# GECBalloonMCUFlightBoard_REV1_0_8-22-18.net
KiCad netlist of a schematic drawn in EAGLE
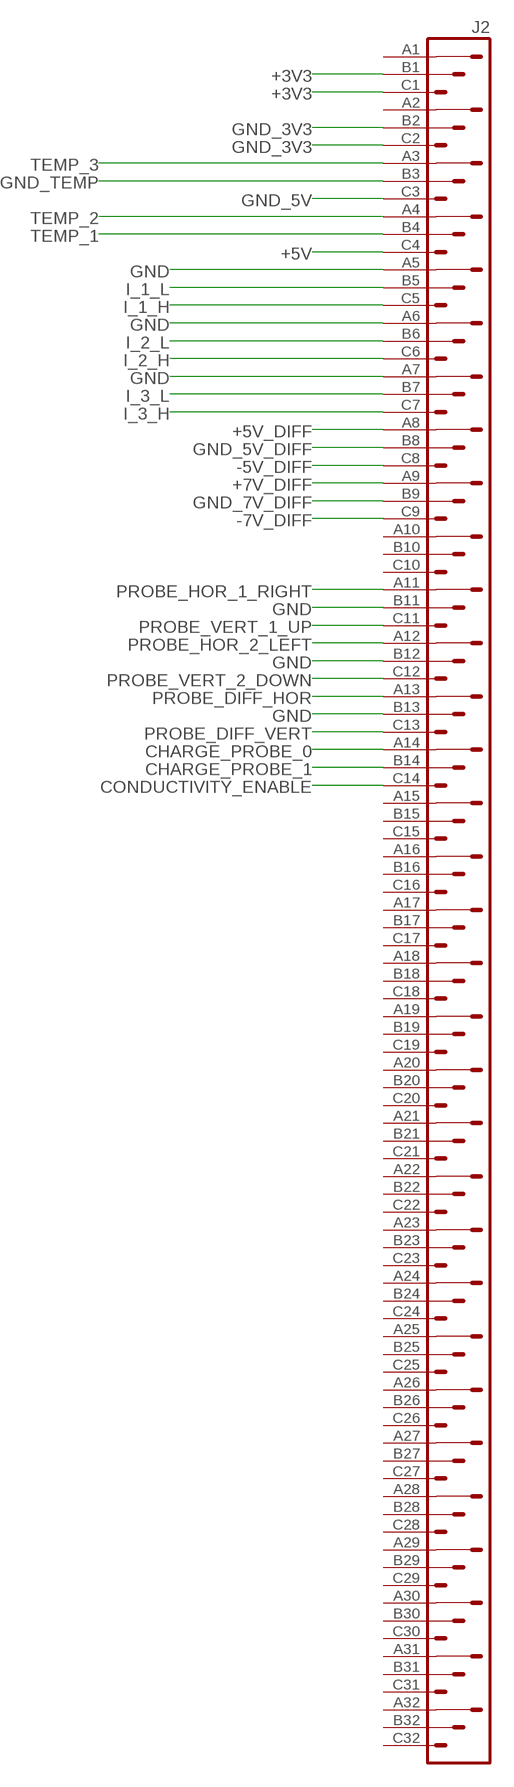
[diagram p0: schematic, sheet 1, part 1 of 2]
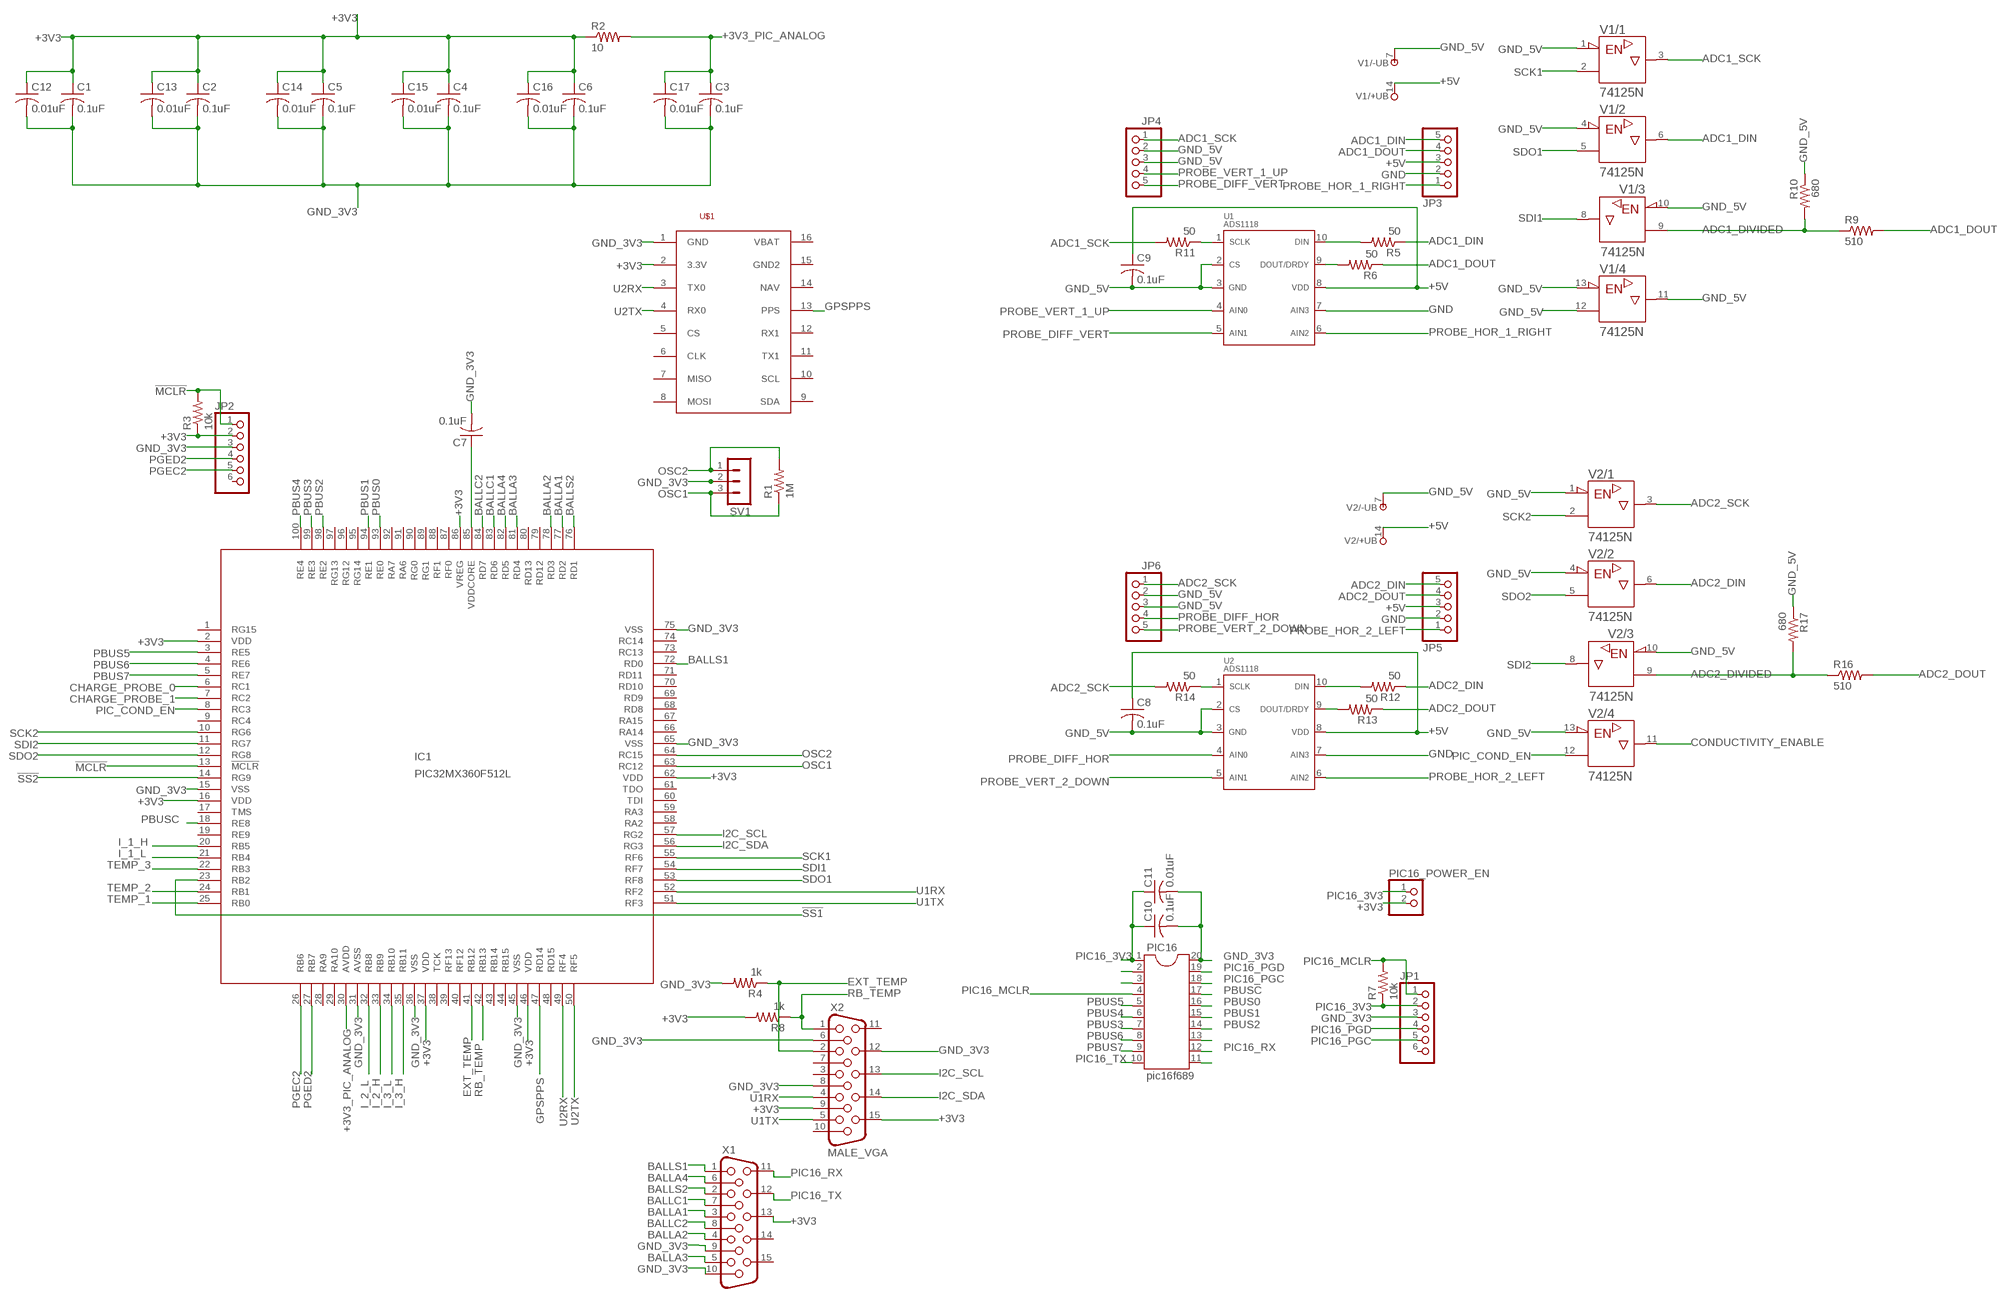
[diagram p1: schematic, sheet 1, part 2 of 2]

(export (version "E")
  (design (tool "Eeschema 10.0.6"))
  (components
    (comp (ref "C1")
      (value "0.1uF")
      (footprint "eagle-import:C1206")
      (libsource (lib "eagle-import") (part "C-USC1206"))
    )
    (comp (ref "C2")
      (value "0.1uF")
      (footprint "eagle-import:C1206")
      (libsource (lib "eagle-import") (part "C-USC1206"))
    )
    (comp (ref "C3")
      (value "0.1uF")
      (footprint "eagle-import:C1206")
      (libsource (lib "eagle-import") (part "C-USC1206"))
    )
    (comp (ref "C4")
      (value "0.1uF")
      (footprint "eagle-import:C1206")
      (libsource (lib "eagle-import") (part "C-USC1206"))
    )
    (comp (ref "C5")
      (value "0.1uF")
      (footprint "eagle-import:C1206")
      (libsource (lib "eagle-import") (part "C-USC1206"))
    )
    (comp (ref "C6")
      (value "0.1uF")
      (footprint "eagle-import:C1206")
      (libsource (lib "eagle-import") (part "C-USC1206"))
    )
    (comp (ref "C7")
      (value "0.1uF")
      (footprint "eagle-import:C1206")
      (libsource (lib "eagle-import") (part "C-USC1206"))
    )
    (comp (ref "C8")
      (value "0.1uF")
      (footprint "eagle-import:C1206")
      (libsource (lib "eagle-import") (part "C-USC1206"))
    )
    (comp (ref "C9")
      (value "0.1uF")
      (footprint "eagle-import:C1206")
      (libsource (lib "eagle-import") (part "C-USC1206"))
    )
    (comp (ref "C10")
      (value "0.1uF")
      (footprint "eagle-import:C1206")
      (libsource (lib "eagle-import") (part "C-USC1206"))
    )
    (comp (ref "C11")
      (value "0.01uF")
      (footprint "eagle-import:C1206")
      (libsource (lib "eagle-import") (part "C-USC1206"))
    )
    (comp (ref "C12")
      (value "0.01uF")
      (footprint "eagle-import:C1206")
      (libsource (lib "eagle-import") (part "C-USC1206"))
    )
    (comp (ref "C13")
      (value "0.01uF")
      (footprint "eagle-import:C1206")
      (libsource (lib "eagle-import") (part "C-USC1206"))
    )
    (comp (ref "C14")
      (value "0.01uF")
      (footprint "eagle-import:C1206")
      (libsource (lib "eagle-import") (part "C-USC1206"))
    )
    (comp (ref "C15")
      (value "0.01uF")
      (footprint "eagle-import:C1206")
      (libsource (lib "eagle-import") (part "C-USC1206"))
    )
    (comp (ref "C16")
      (value "0.01uF")
      (footprint "eagle-import:C1206")
      (libsource (lib "eagle-import") (part "C-USC1206"))
    )
    (comp (ref "C17")
      (value "0.01uF")
      (footprint "eagle-import:C1206")
      (libsource (lib "eagle-import") (part "C-USC1206"))
    )
    (comp (ref "IC1")
      (value "PIC32MX360F512L")
      (footprint "eagle-import:TQFP100")
      (libsource (lib "eagle-import") (part "PIC32MX360F512L"))
    )
    (comp (ref "J2")
      (value "VG96KB")
      (footprint "eagle-import:VG96KB")
      (libsource (lib "eagle-import") (part "VG96KB"))
    )
    (comp (ref "JP1")
      (value "PINHD-1X6")
      (footprint "eagle-import:1X06")
      (libsource (lib "eagle-import") (part "PINHD-1X6"))
    )
    (comp (ref "JP2")
      (value "PINHD-1X6")
      (footprint "eagle-import:1X06")
      (libsource (lib "eagle-import") (part "PINHD-1X6"))
    )
    (comp (ref "JP3")
      (value "PINHD-1X5")
      (footprint "eagle-import:1X05")
      (libsource (lib "eagle-import") (part "PINHD-1X5"))
    )
    (comp (ref "JP4")
      (value "PINHD-1X5")
      (footprint "eagle-import:1X05")
      (libsource (lib "eagle-import") (part "PINHD-1X5"))
    )
    (comp (ref "JP5")
      (value "PINHD-1X5")
      (footprint "eagle-import:1X05")
      (libsource (lib "eagle-import") (part "PINHD-1X5"))
    )
    (comp (ref "JP6")
      (value "PINHD-1X5")
      (footprint "eagle-import:1X05")
      (libsource (lib "eagle-import") (part "PINHD-1X5"))
    )
    (comp (ref "PIC16")
      (value "pic16f689")
      (footprint "eagle-import:DIL20")
      (libsource (lib "eagle-import") (part "DIL20"))
    )
    (comp (ref "PIC16_POWER_EN")
      (value "PINHD-1X2")
      (footprint "eagle-import:1X02")
      (libsource (lib "eagle-import") (part "PINHD-1X2"))
    )
    (comp (ref "R1")
      (value "1M")
      (footprint "eagle-import:M1206")
      (libsource (lib "eagle-import") (part "R-US_M1206"))
    )
    (comp (ref "R2")
      (value "10")
      (footprint "eagle-import:M1206")
      (libsource (lib "eagle-import") (part "R-US_M1206"))
    )
    (comp (ref "R3")
      (value "10k")
      (footprint "eagle-import:M1206")
      (libsource (lib "eagle-import") (part "R-US_M1206"))
    )
    (comp (ref "R4")
      (value "1k")
      (footprint "eagle-import:0414_15")
      (libsource (lib "eagle-import") (part "resistor_R-US_0414/15"))
    )
    (comp (ref "R5")
      (value "50")
      (footprint "eagle-import:M1206")
      (libsource (lib "eagle-import") (part "R-US_M1206"))
    )
    (comp (ref "R6")
      (value "50")
      (footprint "eagle-import:M1206")
      (libsource (lib "eagle-import") (part "R-US_M1206"))
    )
    (comp (ref "R7")
      (value "10k")
      (footprint "eagle-import:M1206")
      (libsource (lib "eagle-import") (part "R-US_M1206"))
    )
    (comp (ref "R8")
      (value "1k")
      (footprint "eagle-import:0414_15")
      (libsource (lib "eagle-import") (part "resistor_R-US_0414/15"))
    )
    (comp (ref "R9")
      (value "510")
      (footprint "eagle-import:R1206")
      (libsource (lib "eagle-import") (part "resistor_R-US_R1206"))
    )
    (comp (ref "R10")
      (value "680")
      (footprint "eagle-import:R1206")
      (libsource (lib "eagle-import") (part "resistor_R-US_R1206"))
    )
    (comp (ref "R11")
      (value "50")
      (footprint "eagle-import:M1206")
      (libsource (lib "eagle-import") (part "R-US_M1206"))
    )
    (comp (ref "R12")
      (value "50")
      (footprint "eagle-import:M1206")
      (libsource (lib "eagle-import") (part "R-US_M1206"))
    )
    (comp (ref "R13")
      (value "50")
      (footprint "eagle-import:M1206")
      (libsource (lib "eagle-import") (part "R-US_M1206"))
    )
    (comp (ref "R14")
      (value "50")
      (footprint "eagle-import:M1206")
      (libsource (lib "eagle-import") (part "R-US_M1206"))
    )
    (comp (ref "R16")
      (value "510")
      (footprint "eagle-import:R1206")
      (libsource (lib "eagle-import") (part "resistor_R-US_R1206"))
    )
    (comp (ref "R17")
      (value "680")
      (footprint "eagle-import:R1206")
      (libsource (lib "eagle-import") (part "resistor_R-US_R1206"))
    )
    (comp (ref "SV1")
      (value "MA03-1")
      (footprint "eagle-import:MA03-1")
      (libsource (lib "eagle-import") (part "MA03-1"))
    )
    (comp (ref "U$1")
      (value "SPARKFUN_VENUS_GPS_BREAKOUT")
      (footprint "eagle-import:SPARKFUN_BOARD")
      (libsource (lib "eagle-import") (part "SPARKFUN_VENUS_GPS_BREAKOUT"))
    )
    (comp (ref "U1")
      (value "ADS1118")
      (footprint "eagle-import:MSOP10")
      (libsource (lib "eagle-import") (part "ADS1118_MSOP10"))
    )
    (comp (ref "U2")
      (value "ADS1118")
      (footprint "eagle-import:MSOP10")
      (libsource (lib "eagle-import") (part "ADS1118_MSOP10"))
    )
    (comp (ref "V1")
      (value "74125N")
      (footprint "eagle-import:DIL14")
      (libsource (lib "eagle-import") (part "74125N"))
    )
    (comp (ref "V2")
      (value "74125N")
      (footprint "eagle-import:DIL14")
      (libsource (lib "eagle-import") (part "74125N"))
    )
    (comp (ref "X1")
      (value "HF15H")
      (footprint "eagle-import:HDF15H")
      (libsource (lib "eagle-import") (part "HF15H"))
    )
    (comp (ref "X2")
      (value "MALE_VGA")
      (footprint "eagle-import:MALE_PACKAGE")
      (libsource (lib "eagle-import") (part "MALE_VGA"))
    )
  )
  (nets
    (net (code "1") (name "/+3V3") (class "Default")
      (node (ref "C1") (pin "1") (pinfunction "1_1") (pintype "passive"))
      (node (ref "C12") (pin "1") (pinfunction "1_1") (pintype "passive"))
      (node (ref "C13") (pin "1") (pinfunction "1_1") (pintype "passive"))
      (node (ref "C14") (pin "1") (pinfunction "1_1") (pintype "passive"))
      (node (ref "C15") (pin "1") (pinfunction "1_1") (pintype "passive"))
      (node (ref "C16") (pin "1") (pinfunction "1_1") (pintype "passive"))
      (node (ref "C2") (pin "1") (pinfunction "1_1") (pintype "passive"))
      (node (ref "C4") (pin "1") (pinfunction "1_1") (pintype "passive"))
      (node (ref "C5") (pin "1") (pinfunction "1_1") (pintype "passive"))
      (node (ref "C6") (pin "1") (pinfunction "1_1") (pintype "passive"))
      (node (ref "IC1") (pin "16") (pinfunction "VDD_16") (pintype "power_in"))
      (node (ref "IC1") (pin "2") (pinfunction "VDD_2") (pintype "power_in"))
      (node (ref "IC1") (pin "37") (pinfunction "VDD_37") (pintype "power_in"))
      (node (ref "IC1") (pin "46") (pinfunction "VDD_46") (pintype "power_in"))
      (node (ref "IC1") (pin "62") (pinfunction "VDD_62") (pintype "power_in"))
      (node (ref "IC1") (pin "86") (pinfunction "VREG_86") (pintype "passive"))
      (node (ref "J2") (pin "B1") (pinfunction "B1_B1") (pintype "passive"))
      (node (ref "J2") (pin "C1") (pinfunction "C1_C1") (pintype "passive"))
      (node (ref "JP2") (pin "2") (pinfunction "2_2") (pintype "passive"))
      (node (ref "PIC16_POWER_EN") (pin "2") (pinfunction "2_2") (pintype "passive"))
      (node (ref "R2") (pin "1") (pinfunction "1_1") (pintype "passive"))
      (node (ref "R3") (pin "1") (pinfunction "1_1") (pintype "passive"))
      (node (ref "R8") (pin "2") (pinfunction "2_2") (pintype "passive"))
      (node (ref "U$1") (pin "2") (pinfunction "3.3V_2") (pintype "bidirectional"))
      (node (ref "X1") (pin "13") (pinfunction "13_13") (pintype "passive"))
      (node (ref "X2") (pin "15") (pinfunction "15_15") (pintype "passive"))
      (node (ref "X2") (pin "9") (pinfunction "9_9") (pintype "passive"))
    )
    (net (code "2") (name "/+3V3_PIC_ANALOG") (class "Default")
      (node (ref "C17") (pin "1") (pinfunction "1_1") (pintype "passive"))
      (node (ref "C3") (pin "1") (pinfunction "1_1") (pintype "passive"))
      (node (ref "IC1") (pin "30") (pinfunction "AVDD_30") (pintype "power_in"))
      (node (ref "R2") (pin "2") (pinfunction "2_2") (pintype "passive"))
    )
    (net (code "3") (name "/+5V") (class "Default")
      (node (ref "C8") (pin "1") (pinfunction "1_1") (pintype "passive"))
      (node (ref "C9") (pin "1") (pinfunction "1_1") (pintype "passive"))
      (node (ref "J2") (pin "C4") (pinfunction "C4_C4") (pintype "passive"))
      (node (ref "JP3") (pin "3") (pinfunction "3_3") (pintype "passive"))
      (node (ref "JP5") (pin "3") (pinfunction "3_3") (pintype "passive"))
      (node (ref "U1") (pin "8") (pinfunction "VDD_8") (pintype "bidirectional"))
      (node (ref "U2") (pin "8") (pinfunction "VDD_8") (pintype "bidirectional"))
      (node (ref "V1") (pin "14") (pinfunction "+UB_14") (pintype "power_in"))
      (node (ref "V2") (pin "14") (pinfunction "+UB_14") (pintype "power_in"))
    )
    (net (code "4") (name "/+5V_DIFF") (class "Default")
      (node (ref "J2") (pin "A8") (pinfunction "A8_A8") (pintype "passive"))
    )
    (net (code "5") (name "/+7V_DIFF") (class "Default")
      (node (ref "J2") (pin "A9") (pinfunction "A9_A9") (pintype "passive"))
    )
    (net (code "6") (name "/-5V_DIFF") (class "Default")
      (node (ref "J2") (pin "C8") (pinfunction "C8_C8") (pintype "passive"))
    )
    (net (code "7") (name "/-7V_DIFF") (class "Default")
      (node (ref "J2") (pin "C9") (pinfunction "C9_C9") (pintype "passive"))
    )
    (net (code "8") (name "/ADC1_DIN") (class "Default")
      (node (ref "JP3") (pin "5") (pinfunction "5_5") (pintype "passive"))
      (node (ref "R5") (pin "1") (pinfunction "1_1") (pintype "passive"))
      (node (ref "V1") (pin "6") (pinfunction "Y_6") (pintype "tri_state"))
    )
    (net (code "9") (name "/ADC1_DIVIDED") (class "Default")
      (node (ref "R10") (pin "2") (pinfunction "2_2") (pintype "passive"))
      (node (ref "R9") (pin "1") (pinfunction "1_1") (pintype "passive"))
      (node (ref "V1") (pin "9") (pinfunction "A_9") (pintype "input"))
    )
    (net (code "10") (name "/ADC1_DOUT") (class "Default")
      (node (ref "JP3") (pin "4") (pinfunction "4_4") (pintype "passive"))
      (node (ref "R6") (pin "1") (pinfunction "1_1") (pintype "passive"))
      (node (ref "R9") (pin "2") (pinfunction "2_2") (pintype "passive"))
    )
    (net (code "11") (name "/ADC1_SCK") (class "Default")
      (node (ref "JP4") (pin "1") (pinfunction "1_1") (pintype "passive"))
      (node (ref "R11") (pin "2") (pinfunction "2_2") (pintype "passive"))
      (node (ref "V1") (pin "3") (pinfunction "Y_3") (pintype "tri_state"))
    )
    (net (code "12") (name "/ADC2_DIN") (class "Default")
      (node (ref "JP5") (pin "5") (pinfunction "5_5") (pintype "passive"))
      (node (ref "R12") (pin "1") (pinfunction "1_1") (pintype "passive"))
      (node (ref "V2") (pin "6") (pinfunction "Y_6") (pintype "tri_state"))
    )
    (net (code "13") (name "/ADC2_DIVIDED") (class "Default")
      (node (ref "R16") (pin "1") (pinfunction "1_1") (pintype "passive"))
      (node (ref "R17") (pin "2") (pinfunction "2_2") (pintype "passive"))
      (node (ref "V2") (pin "9") (pinfunction "A_9") (pintype "input"))
    )
    (net (code "14") (name "/ADC2_DOUT") (class "Default")
      (node (ref "JP5") (pin "4") (pinfunction "4_4") (pintype "passive"))
      (node (ref "R13") (pin "1") (pinfunction "1_1") (pintype "passive"))
      (node (ref "R16") (pin "2") (pinfunction "2_2") (pintype "passive"))
    )
    (net (code "15") (name "/ADC2_SCK") (class "Default")
      (node (ref "JP6") (pin "1") (pinfunction "1_1") (pintype "passive"))
      (node (ref "R14") (pin "2") (pinfunction "2_2") (pintype "passive"))
      (node (ref "V2") (pin "3") (pinfunction "Y_3") (pintype "tri_state"))
    )
    (net (code "16") (name "/BALLA1") (class "Default")
      (node (ref "IC1") (pin "77") (pinfunction "RD2_77") (pintype "bidirectional"))
      (node (ref "X1") (pin "3") (pinfunction "3_3") (pintype "passive"))
    )
    (net (code "17") (name "/BALLA2") (class "Default")
      (node (ref "IC1") (pin "78") (pinfunction "RD3_78") (pintype "bidirectional"))
      (node (ref "X1") (pin "4") (pinfunction "4_4") (pintype "passive"))
    )
    (net (code "18") (name "/BALLA3") (class "Default")
      (node (ref "IC1") (pin "81") (pinfunction "RD4_81") (pintype "bidirectional"))
      (node (ref "X1") (pin "5") (pinfunction "5_5") (pintype "passive"))
    )
    (net (code "19") (name "/BALLA4") (class "Default")
      (node (ref "IC1") (pin "82") (pinfunction "RD5_82") (pintype "bidirectional"))
      (node (ref "X1") (pin "6") (pinfunction "6_6") (pintype "passive"))
    )
    (net (code "20") (name "/BALLC1") (class "Default")
      (node (ref "IC1") (pin "83") (pinfunction "RD6_83") (pintype "bidirectional"))
      (node (ref "X1") (pin "7") (pinfunction "7_7") (pintype "passive"))
    )
    (net (code "21") (name "/BALLC2") (class "Default")
      (node (ref "IC1") (pin "84") (pinfunction "RD7_84") (pintype "bidirectional"))
      (node (ref "X1") (pin "8") (pinfunction "8_8") (pintype "passive"))
    )
    (net (code "22") (name "/BALLS1") (class "Default")
      (node (ref "IC1") (pin "72") (pinfunction "RD0_72") (pintype "bidirectional"))
      (node (ref "X1") (pin "1") (pinfunction "1_1") (pintype "passive"))
    )
    (net (code "23") (name "/BALLS2") (class "Default")
      (node (ref "IC1") (pin "76") (pinfunction "RD1_76") (pintype "bidirectional"))
      (node (ref "X1") (pin "2") (pinfunction "2_2") (pintype "passive"))
    )
    (net (code "24") (name "/CHARGE_PROBE_0") (class "Default")
      (node (ref "IC1") (pin "6") (pinfunction "RC1_6") (pintype "bidirectional"))
      (node (ref "J2") (pin "A14") (pinfunction "A14_A14") (pintype "passive"))
    )
    (net (code "25") (name "/CHARGE_PROBE_1") (class "Default")
      (node (ref "IC1") (pin "7") (pinfunction "RC2_7") (pintype "bidirectional"))
      (node (ref "J2") (pin "B14") (pinfunction "B14_B14") (pintype "passive"))
    )
    (net (code "26") (name "/CONDUCTIVITY_ENABLE") (class "Default")
      (node (ref "J2") (pin "C14") (pinfunction "C14_C14") (pintype "passive"))
      (node (ref "V2") (pin "11") (pinfunction "Y_11") (pintype "tri_state"))
    )
    (net (code "27") (name "/EXT_TEMP") (class "Default")
      (node (ref "IC1") (pin "41") (pinfunction "RB12_41") (pintype "bidirectional"))
      (node (ref "R4") (pin "1") (pinfunction "1_1") (pintype "passive"))
      (node (ref "X2") (pin "2") (pinfunction "2_2") (pintype "passive"))
    )
    (net (code "28") (name "/GND") (class "Default")
      (node (ref "J2") (pin "A5") (pinfunction "A5_A5") (pintype "passive"))
      (node (ref "J2") (pin "A6") (pinfunction "A6_A6") (pintype "passive"))
      (node (ref "J2") (pin "A7") (pinfunction "A7_A7") (pintype "passive"))
      (node (ref "J2") (pin "B11") (pinfunction "B11_B11") (pintype "passive"))
      (node (ref "J2") (pin "B12") (pinfunction "B12_B12") (pintype "passive"))
      (node (ref "J2") (pin "B13") (pinfunction "B13_B13") (pintype "passive"))
      (node (ref "JP3") (pin "2") (pinfunction "2_2") (pintype "passive"))
      (node (ref "JP5") (pin "2") (pinfunction "2_2") (pintype "passive"))
      (node (ref "U1") (pin "7") (pinfunction "AIN3_7") (pintype "bidirectional"))
      (node (ref "U2") (pin "7") (pinfunction "AIN3_7") (pintype "bidirectional"))
    )
    (net (code "29") (name "/GND_3V3") (class "Default")
      (node (ref "C1") (pin "2") (pinfunction "2_2") (pintype "passive"))
      (node (ref "C10") (pin "2") (pinfunction "2_2") (pintype "passive"))
      (node (ref "C11") (pin "2") (pinfunction "2_2") (pintype "passive"))
      (node (ref "C12") (pin "2") (pinfunction "2_2") (pintype "passive"))
      (node (ref "C13") (pin "2") (pinfunction "2_2") (pintype "passive"))
      (node (ref "C14") (pin "2") (pinfunction "2_2") (pintype "passive"))
      (node (ref "C15") (pin "2") (pinfunction "2_2") (pintype "passive"))
      (node (ref "C16") (pin "2") (pinfunction "2_2") (pintype "passive"))
      (node (ref "C17") (pin "2") (pinfunction "2_2") (pintype "passive"))
      (node (ref "C2") (pin "2") (pinfunction "2_2") (pintype "passive"))
      (node (ref "C3") (pin "2") (pinfunction "2_2") (pintype "passive"))
      (node (ref "C4") (pin "2") (pinfunction "2_2") (pintype "passive"))
      (node (ref "C5") (pin "2") (pinfunction "2_2") (pintype "passive"))
      (node (ref "C6") (pin "2") (pinfunction "2_2") (pintype "passive"))
      (node (ref "C7") (pin "2") (pinfunction "2_2") (pintype "passive"))
      (node (ref "IC1") (pin "15") (pinfunction "VSS_15") (pintype "power_in"))
      (node (ref "IC1") (pin "31") (pinfunction "AVSS_31") (pintype "power_in"))
      (node (ref "IC1") (pin "36") (pinfunction "VSS_36") (pintype "power_in"))
      (node (ref "IC1") (pin "45") (pinfunction "VSS_45") (pintype "power_in"))
      (node (ref "IC1") (pin "65") (pinfunction "VSS_65") (pintype "power_in"))
      (node (ref "IC1") (pin "75") (pinfunction "VSS_75") (pintype "power_in"))
      (node (ref "J2") (pin "B2") (pinfunction "B2_B2") (pintype "passive"))
      (node (ref "J2") (pin "C2") (pinfunction "C2_C2") (pintype "passive"))
      (node (ref "JP1") (pin "3") (pinfunction "3_3") (pintype "passive"))
      (node (ref "JP2") (pin "3") (pinfunction "3_3") (pintype "passive"))
      (node (ref "PIC16") (pin "20") (pinfunction "20_20") (pintype "passive"))
      (node (ref "R4") (pin "2") (pinfunction "2_2") (pintype "passive"))
      (node (ref "SV1") (pin "2") (pinfunction "2_2") (pintype "passive"))
      (node (ref "U$1") (pin "1") (pinfunction "GND_1") (pintype "bidirectional"))
      (node (ref "X1") (pin "10") (pinfunction "10_10") (pintype "passive"))
      (node (ref "X1") (pin "9") (pinfunction "9_9") (pintype "passive"))
      (node (ref "X2") (pin "12") (pinfunction "12_12") (pintype "passive"))
      (node (ref "X2") (pin "6") (pinfunction "6_6") (pintype "passive"))
      (node (ref "X2") (pin "8") (pinfunction "8_8") (pintype "passive"))
    )
    (net (code "30") (name "/GND_5V") (class "Default")
      (node (ref "C8") (pin "2") (pinfunction "2_2") (pintype "passive"))
      (node (ref "C9") (pin "2") (pinfunction "2_2") (pintype "passive"))
      (node (ref "J2") (pin "C3") (pinfunction "C3_C3") (pintype "passive"))
      (node (ref "JP4") (pin "2") (pinfunction "2_2") (pintype "passive"))
      (node (ref "JP4") (pin "3") (pinfunction "3_3") (pintype "passive"))
      (node (ref "JP6") (pin "2") (pinfunction "2_2") (pintype "passive"))
      (node (ref "JP6") (pin "3") (pinfunction "3_3") (pintype "passive"))
      (node (ref "R10") (pin "1") (pinfunction "1_1") (pintype "passive"))
      (node (ref "R17") (pin "1") (pinfunction "1_1") (pintype "passive"))
      (node (ref "U1") (pin "2") (pinfunction "CS_2") (pintype "bidirectional"))
      (node (ref "U1") (pin "3") (pinfunction "GND_3") (pintype "bidirectional"))
      (node (ref "U2") (pin "2") (pinfunction "CS_2") (pintype "bidirectional"))
      (node (ref "U2") (pin "3") (pinfunction "GND_3") (pintype "bidirectional"))
      (node (ref "V1") (pin "1") (pinfunction "~{G}_1") (pintype "input"))
      (node (ref "V1") (pin "10") (pinfunction "~{G}_10") (pintype "input"))
      (node (ref "V1") (pin "11") (pinfunction "Y_11") (pintype "tri_state"))
      (node (ref "V1") (pin "12") (pinfunction "A_12") (pintype "input"))
      (node (ref "V1") (pin "13") (pinfunction "~{G}_13") (pintype "input"))
      (node (ref "V1") (pin "4") (pinfunction "~{G}_4") (pintype "input"))
      (node (ref "V1") (pin "7") (pinfunction "-UB_7") (pintype "power_in"))
      (node (ref "V2") (pin "1") (pinfunction "~{G}_1") (pintype "input"))
      (node (ref "V2") (pin "10") (pinfunction "~{G}_10") (pintype "input"))
      (node (ref "V2") (pin "13") (pinfunction "~{G}_13") (pintype "input"))
      (node (ref "V2") (pin "4") (pinfunction "~{G}_4") (pintype "input"))
      (node (ref "V2") (pin "7") (pinfunction "-UB_7") (pintype "power_in"))
    )
    (net (code "31") (name "/GND_5V_DIFF") (class "Default")
      (node (ref "J2") (pin "B8") (pinfunction "B8_B8") (pintype "passive"))
    )
    (net (code "32") (name "/GND_7V_DIFF") (class "Default")
      (node (ref "J2") (pin "B9") (pinfunction "B9_B9") (pintype "passive"))
    )
    (net (code "33") (name "/GND_TEMP") (class "Default")
      (node (ref "J2") (pin "B3") (pinfunction "B3_B3") (pintype "passive"))
    )
    (net (code "34") (name "/GPSPPS") (class "Default")
      (node (ref "IC1") (pin "47") (pinfunction "RD14_47") (pintype "bidirectional"))
      (node (ref "U$1") (pin "13") (pinfunction "PPS_13") (pintype "bidirectional"))
    )
    (net (code "35") (name "/I2C_SCL") (class "Default")
      (node (ref "IC1") (pin "57") (pinfunction "RG2_57") (pintype "bidirectional"))
      (node (ref "X2") (pin "13") (pinfunction "13_13") (pintype "passive"))
    )
    (net (code "36") (name "/I2C_SDA") (class "Default")
      (node (ref "IC1") (pin "56") (pinfunction "RG3_56") (pintype "bidirectional"))
      (node (ref "X2") (pin "14") (pinfunction "14_14") (pintype "passive"))
    )
    (net (code "37") (name "/I_1_H") (class "Default")
      (node (ref "IC1") (pin "20") (pinfunction "RB5_20") (pintype "bidirectional"))
      (node (ref "J2") (pin "C5") (pinfunction "C5_C5") (pintype "passive"))
    )
    (net (code "38") (name "/I_1_L") (class "Default")
      (node (ref "IC1") (pin "21") (pinfunction "RB4_21") (pintype "bidirectional"))
      (node (ref "J2") (pin "B5") (pinfunction "B5_B5") (pintype "passive"))
    )
    (net (code "39") (name "/I_2_H") (class "Default")
      (node (ref "IC1") (pin "33") (pinfunction "RB9_33") (pintype "bidirectional"))
      (node (ref "J2") (pin "C6") (pinfunction "C6_C6") (pintype "passive"))
    )
    (net (code "40") (name "/I_2_L") (class "Default")
      (node (ref "IC1") (pin "32") (pinfunction "RB8_32") (pintype "bidirectional"))
      (node (ref "J2") (pin "B6") (pinfunction "B6_B6") (pintype "passive"))
    )
    (net (code "41") (name "/I_3_H") (class "Default")
      (node (ref "IC1") (pin "35") (pinfunction "RB11_35") (pintype "bidirectional"))
      (node (ref "J2") (pin "C7") (pinfunction "C7_C7") (pintype "passive"))
    )
    (net (code "42") (name "/I_3_L") (class "Default")
      (node (ref "IC1") (pin "34") (pinfunction "RB10_34") (pintype "bidirectional"))
      (node (ref "J2") (pin "B7") (pinfunction "B7_B7") (pintype "passive"))
    )
    (net (code "43") (name "/OSC1") (class "Default")
      (node (ref "IC1") (pin "63") (pinfunction "RC12_63") (pintype "bidirectional"))
      (node (ref "R1") (pin "1") (pinfunction "1_1") (pintype "passive"))
      (node (ref "SV1") (pin "3") (pinfunction "3_3") (pintype "passive"))
    )
    (net (code "44") (name "/OSC2") (class "Default")
      (node (ref "IC1") (pin "64") (pinfunction "RC15_64") (pintype "bidirectional"))
      (node (ref "R1") (pin "2") (pinfunction "2_2") (pintype "passive"))
      (node (ref "SV1") (pin "1") (pinfunction "1_1") (pintype "passive"))
    )
    (net (code "45") (name "/PBUS0") (class "Default")
      (node (ref "IC1") (pin "93") (pinfunction "RE0_93") (pintype "bidirectional"))
      (node (ref "PIC16") (pin "16") (pinfunction "16_16") (pintype "passive"))
    )
    (net (code "46") (name "/PBUS1") (class "Default")
      (node (ref "IC1") (pin "94") (pinfunction "RE1_94") (pintype "bidirectional"))
      (node (ref "PIC16") (pin "15") (pinfunction "15_15") (pintype "passive"))
    )
    (net (code "47") (name "/PBUS2") (class "Default")
      (node (ref "IC1") (pin "98") (pinfunction "RE2_98") (pintype "bidirectional"))
      (node (ref "PIC16") (pin "14") (pinfunction "14_14") (pintype "passive"))
    )
    (net (code "48") (name "/PBUS3") (class "Default")
      (node (ref "IC1") (pin "99") (pinfunction "RE3_99") (pintype "bidirectional"))
      (node (ref "PIC16") (pin "7") (pinfunction "7_7") (pintype "passive"))
    )
    (net (code "49") (name "/PBUS4") (class "Default")
      (node (ref "IC1") (pin "100") (pinfunction "RE4_100") (pintype "bidirectional"))
      (node (ref "PIC16") (pin "6") (pinfunction "6_6") (pintype "passive"))
    )
    (net (code "50") (name "/PBUS5") (class "Default")
      (node (ref "IC1") (pin "3") (pinfunction "RE5_3") (pintype "bidirectional"))
      (node (ref "PIC16") (pin "5") (pinfunction "5_5") (pintype "passive"))
    )
    (net (code "51") (name "/PBUS6") (class "Default")
      (node (ref "IC1") (pin "4") (pinfunction "RE6_4") (pintype "bidirectional"))
      (node (ref "PIC16") (pin "8") (pinfunction "8_8") (pintype "passive"))
    )
    (net (code "52") (name "/PBUS7") (class "Default")
      (node (ref "IC1") (pin "5") (pinfunction "RE7_5") (pintype "bidirectional"))
      (node (ref "PIC16") (pin "9") (pinfunction "9_9") (pintype "passive"))
    )
    (net (code "53") (name "/PBUSC") (class "Default")
      (node (ref "IC1") (pin "18") (pinfunction "RE8_18") (pintype "bidirectional"))
      (node (ref "PIC16") (pin "17") (pinfunction "17_17") (pintype "passive"))
    )
    (net (code "54") (name "/PGEC2") (class "Default")
      (node (ref "IC1") (pin "26") (pinfunction "RB6_26") (pintype "bidirectional"))
      (node (ref "JP2") (pin "5") (pinfunction "5_5") (pintype "passive"))
    )
    (net (code "55") (name "/PGED2") (class "Default")
      (node (ref "IC1") (pin "27") (pinfunction "RB7_27") (pintype "bidirectional"))
      (node (ref "JP2") (pin "4") (pinfunction "4_4") (pintype "passive"))
    )
    (net (code "56") (name "/PIC16_3V3") (class "Default")
      (node (ref "C10") (pin "1") (pinfunction "1_1") (pintype "passive"))
      (node (ref "C11") (pin "1") (pinfunction "1_1") (pintype "passive"))
      (node (ref "JP1") (pin "2") (pinfunction "2_2") (pintype "passive"))
      (node (ref "PIC16") (pin "1") (pinfunction "1_1") (pintype "passive"))
      (node (ref "PIC16_POWER_EN") (pin "1") (pinfunction "1_1") (pintype "passive"))
      (node (ref "R7") (pin "1") (pinfunction "1_1") (pintype "passive"))
    )
    (net (code "57") (name "/PIC16_MCLR") (class "Default")
      (node (ref "JP1") (pin "1") (pinfunction "1_1") (pintype "passive"))
      (node (ref "PIC16") (pin "4") (pinfunction "4_4") (pintype "passive"))
      (node (ref "R7") (pin "2") (pinfunction "2_2") (pintype "passive"))
    )
    (net (code "58") (name "/PIC16_PGC") (class "Default")
      (node (ref "JP1") (pin "5") (pinfunction "5_5") (pintype "passive"))
      (node (ref "PIC16") (pin "18") (pinfunction "18_18") (pintype "passive"))
    )
    (net (code "59") (name "/PIC16_PGD") (class "Default")
      (node (ref "JP1") (pin "4") (pinfunction "4_4") (pintype "passive"))
      (node (ref "PIC16") (pin "19") (pinfunction "19_19") (pintype "passive"))
    )
    (net (code "60") (name "/PIC16_RX") (class "Default")
      (node (ref "PIC16") (pin "12") (pinfunction "12_12") (pintype "passive"))
      (node (ref "X1") (pin "11") (pinfunction "11_11") (pintype "passive"))
    )
    (net (code "61") (name "/PIC16_TX") (class "Default")
      (node (ref "PIC16") (pin "10") (pinfunction "10_10") (pintype "passive"))
      (node (ref "X1") (pin "12") (pinfunction "12_12") (pintype "passive"))
    )
    (net (code "62") (name "/PIC_COND_EN") (class "Default")
      (node (ref "IC1") (pin "8") (pinfunction "RC3_8") (pintype "bidirectional"))
      (node (ref "V2") (pin "12") (pinfunction "A_12") (pintype "input"))
    )
    (net (code "63") (name "/PROBE_DIFF_HOR") (class "Default")
      (node (ref "J2") (pin "A13") (pinfunction "A13_A13") (pintype "passive"))
      (node (ref "JP6") (pin "4") (pinfunction "4_4") (pintype "passive"))
      (node (ref "U2") (pin "4") (pinfunction "AIN0_4") (pintype "bidirectional"))
    )
    (net (code "64") (name "/PROBE_DIFF_VERT") (class "Default")
      (node (ref "J2") (pin "C13") (pinfunction "C13_C13") (pintype "passive"))
      (node (ref "JP4") (pin "5") (pinfunction "5_5") (pintype "passive"))
      (node (ref "U1") (pin "5") (pinfunction "AIN1_5") (pintype "bidirectional"))
    )
    (net (code "65") (name "/PROBE_HOR_1_RIGHT") (class "Default")
      (node (ref "J2") (pin "A11") (pinfunction "A11_A11") (pintype "passive"))
      (node (ref "JP3") (pin "1") (pinfunction "1_1") (pintype "passive"))
      (node (ref "U1") (pin "6") (pinfunction "AIN2_6") (pintype "bidirectional"))
    )
    (net (code "66") (name "/PROBE_HOR_2_LEFT") (class "Default")
      (node (ref "J2") (pin "A12") (pinfunction "A12_A12") (pintype "passive"))
      (node (ref "JP5") (pin "1") (pinfunction "1_1") (pintype "passive"))
      (node (ref "U2") (pin "6") (pinfunction "AIN2_6") (pintype "bidirectional"))
    )
    (net (code "67") (name "/PROBE_VERT_1_UP") (class "Default")
      (node (ref "J2") (pin "C11") (pinfunction "C11_C11") (pintype "passive"))
      (node (ref "JP4") (pin "4") (pinfunction "4_4") (pintype "passive"))
      (node (ref "U1") (pin "4") (pinfunction "AIN0_4") (pintype "bidirectional"))
    )
    (net (code "68") (name "/PROBE_VERT_2_DOWN") (class "Default")
      (node (ref "J2") (pin "C12") (pinfunction "C12_C12") (pintype "passive"))
      (node (ref "JP6") (pin "5") (pinfunction "5_5") (pintype "passive"))
      (node (ref "U2") (pin "5") (pinfunction "AIN1_5") (pintype "bidirectional"))
    )
    (net (code "69") (name "/RB_TEMP") (class "Default")
      (node (ref "IC1") (pin "42") (pinfunction "RB13_42") (pintype "bidirectional"))
      (node (ref "R8") (pin "1") (pinfunction "1_1") (pintype "passive"))
      (node (ref "X2") (pin "1") (pinfunction "1_1") (pintype "passive"))
    )
    (net (code "70") (name "/SCK1") (class "Default")
      (node (ref "IC1") (pin "55") (pinfunction "RF6_55") (pintype "bidirectional"))
      (node (ref "V1") (pin "2") (pinfunction "A_2") (pintype "input"))
    )
    (net (code "71") (name "/SCK2") (class "Default")
      (node (ref "IC1") (pin "10") (pinfunction "RG6_10") (pintype "bidirectional"))
      (node (ref "V2") (pin "2") (pinfunction "A_2") (pintype "input"))
    )
    (net (code "72") (name "/SDI1") (class "Default")
      (node (ref "IC1") (pin "54") (pinfunction "RF7_54") (pintype "bidirectional"))
      (node (ref "V1") (pin "8") (pinfunction "Y_8") (pintype "tri_state"))
    )
    (net (code "73") (name "/SDI2") (class "Default")
      (node (ref "IC1") (pin "11") (pinfunction "RG7_11") (pintype "bidirectional"))
      (node (ref "V2") (pin "8") (pinfunction "Y_8") (pintype "tri_state"))
    )
    (net (code "74") (name "/SDO1") (class "Default")
      (node (ref "IC1") (pin "53") (pinfunction "RF8_53") (pintype "bidirectional"))
      (node (ref "V1") (pin "5") (pinfunction "A_5") (pintype "input"))
    )
    (net (code "75") (name "/SDO2") (class "Default")
      (node (ref "IC1") (pin "12") (pinfunction "RG8_12") (pintype "bidirectional"))
      (node (ref "V2") (pin "5") (pinfunction "A_5") (pintype "input"))
    )
    (net (code "76") (name "/TEMP_1") (class "Default")
      (node (ref "IC1") (pin "25") (pinfunction "RB0_25") (pintype "bidirectional"))
      (node (ref "J2") (pin "B4") (pinfunction "B4_B4") (pintype "passive"))
    )
    (net (code "77") (name "/TEMP_2") (class "Default")
      (node (ref "IC1") (pin "24") (pinfunction "RB1_24") (pintype "bidirectional"))
      (node (ref "J2") (pin "A4") (pinfunction "A4_A4") (pintype "passive"))
    )
    (net (code "78") (name "/TEMP_3") (class "Default")
      (node (ref "IC1") (pin "22") (pinfunction "RB3_22") (pintype "bidirectional"))
      (node (ref "J2") (pin "A3") (pinfunction "A3_A3") (pintype "passive"))
    )
    (net (code "79") (name "/U1RX") (class "Default")
      (node (ref "IC1") (pin "52") (pinfunction "RF2_52") (pintype "bidirectional"))
      (node (ref "X2") (pin "4") (pinfunction "4_4") (pintype "passive"))
    )
    (net (code "80") (name "/U1TX") (class "Default")
      (node (ref "IC1") (pin "51") (pinfunction "RF3_51") (pintype "bidirectional"))
      (node (ref "X2") (pin "5") (pinfunction "5_5") (pintype "passive"))
    )
    (net (code "81") (name "/U2RX") (class "Default")
      (node (ref "IC1") (pin "49") (pinfunction "RF4_49") (pintype "bidirectional"))
      (node (ref "U$1") (pin "3") (pinfunction "TX0_3") (pintype "bidirectional"))
    )
    (net (code "82") (name "/U2TX") (class "Default")
      (node (ref "IC1") (pin "50") (pinfunction "RF5_50") (pintype "bidirectional"))
      (node (ref "U$1") (pin "4") (pinfunction "RX0_4") (pintype "bidirectional"))
    )
    (net (code "83") (name "/~{MCLR}") (class "Default")
      (node (ref "IC1") (pin "13") (pinfunction "~{MCLR}_13") (pintype "input"))
      (node (ref "JP2") (pin "1") (pinfunction "1_1") (pintype "passive"))
      (node (ref "R3") (pin "2") (pinfunction "2_2") (pintype "passive"))
    )
    (net (code "84") (name "/~{SS1}") (class "Default")
      (node (ref "IC1") (pin "23") (pinfunction "RB2_23") (pintype "bidirectional"))
    )
    (net (code "85") (name "/~{SS2}") (class "Default")
      (node (ref "IC1") (pin "14") (pinfunction "RG9_14") (pintype "bidirectional"))
    )
    (net (code "86") (name "Net-(IC1-VDDCORE)") (class "Default")
      (node (ref "C7") (pin "1") (pinfunction "1_1") (pintype "passive"))
      (node (ref "IC1") (pin "85") (pinfunction "VDDCORE_85") (pintype "power_in"))
    )
    (net (code "87") (name "Net-(U1-DIN)") (class "Default")
      (node (ref "R5") (pin "2") (pinfunction "2_2") (pintype "passive"))
      (node (ref "U1") (pin "10") (pinfunction "DIN_10") (pintype "bidirectional"))
    )
    (net (code "88") (name "Net-(U1-DOUT{slash}DRDY)") (class "Default")
      (node (ref "R6") (pin "2") (pinfunction "2_2") (pintype "passive"))
      (node (ref "U1") (pin "9") (pinfunction "DOUT/DRDY_9") (pintype "bidirectional"))
    )
    (net (code "89") (name "Net-(U1-SCLK)") (class "Default")
      (node (ref "R11") (pin "1") (pinfunction "1_1") (pintype "passive"))
      (node (ref "U1") (pin "1") (pinfunction "SCLK_1") (pintype "bidirectional"))
    )
    (net (code "90") (name "Net-(U2-DIN)") (class "Default")
      (node (ref "R12") (pin "2") (pinfunction "2_2") (pintype "passive"))
      (node (ref "U2") (pin "10") (pinfunction "DIN_10") (pintype "bidirectional"))
    )
    (net (code "91") (name "Net-(U2-DOUT{slash}DRDY)") (class "Default")
      (node (ref "R13") (pin "2") (pinfunction "2_2") (pintype "passive"))
      (node (ref "U2") (pin "9") (pinfunction "DOUT/DRDY_9") (pintype "bidirectional"))
    )
    (net (code "92") (name "Net-(U2-SCLK)") (class "Default")
      (node (ref "R14") (pin "1") (pinfunction "1_1") (pintype "passive"))
      (node (ref "U2") (pin "1") (pinfunction "SCLK_1") (pintype "bidirectional"))
    )
    (net (code "93") (name "unconnected-(IC1-RA2-Pad58)") (class "Default")
      (node (ref "IC1") (pin "58") (pinfunction "RA2_58") (pintype "bidirectional"))
    )
    (net (code "94") (name "unconnected-(IC1-RA3-Pad59)") (class "Default")
      (node (ref "IC1") (pin "59") (pinfunction "RA3_59") (pintype "bidirectional"))
    )
    (net (code "95") (name "unconnected-(IC1-RA6-Pad91)") (class "Default")
      (node (ref "IC1") (pin "91") (pinfunction "RA6_91") (pintype "bidirectional"))
    )
    (net (code "96") (name "unconnected-(IC1-RA7-Pad92)") (class "Default")
      (node (ref "IC1") (pin "92") (pinfunction "RA7_92") (pintype "bidirectional"))
    )
    (net (code "97") (name "unconnected-(IC1-RA9-Pad28)") (class "Default")
      (node (ref "IC1") (pin "28") (pinfunction "RA9_28") (pintype "bidirectional"))
    )
    (net (code "98") (name "unconnected-(IC1-RA10-Pad29)") (class "Default")
      (node (ref "IC1") (pin "29") (pinfunction "RA10_29") (pintype "bidirectional"))
    )
    (net (code "99") (name "unconnected-(IC1-RA14-Pad66)") (class "Default")
      (node (ref "IC1") (pin "66") (pinfunction "RA14_66") (pintype "bidirectional"))
    )
    (net (code "100") (name "unconnected-(IC1-RA15-Pad67)") (class "Default")
      (node (ref "IC1") (pin "67") (pinfunction "RA15_67") (pintype "bidirectional"))
    )
    (net (code "101") (name "unconnected-(IC1-RB14-Pad43)") (class "Default")
      (node (ref "IC1") (pin "43") (pinfunction "RB14_43") (pintype "bidirectional"))
    )
    (net (code "102") (name "unconnected-(IC1-RB15-Pad44)") (class "Default")
      (node (ref "IC1") (pin "44") (pinfunction "RB15_44") (pintype "bidirectional"))
    )
    (net (code "103") (name "unconnected-(IC1-RC4-Pad9)") (class "Default")
      (node (ref "IC1") (pin "9") (pinfunction "RC4_9") (pintype "bidirectional"))
    )
    (net (code "104") (name "unconnected-(IC1-RC13-Pad73)") (class "Default")
      (node (ref "IC1") (pin "73") (pinfunction "RC13_73") (pintype "bidirectional"))
    )
    (net (code "105") (name "unconnected-(IC1-RC14-Pad74)") (class "Default")
      (node (ref "IC1") (pin "74") (pinfunction "RC14_74") (pintype "bidirectional"))
    )
    (net (code "106") (name "unconnected-(IC1-RD8-Pad68)") (class "Default")
      (node (ref "IC1") (pin "68") (pinfunction "RD8_68") (pintype "bidirectional"))
    )
    (net (code "107") (name "unconnected-(IC1-RD9-Pad69)") (class "Default")
      (node (ref "IC1") (pin "69") (pinfunction "RD9_69") (pintype "bidirectional"))
    )
    (net (code "108") (name "unconnected-(IC1-RD10-Pad70)") (class "Default")
      (node (ref "IC1") (pin "70") (pinfunction "RD10_70") (pintype "bidirectional"))
    )
    (net (code "109") (name "unconnected-(IC1-RD11-Pad71)") (class "Default")
      (node (ref "IC1") (pin "71") (pinfunction "RD11_71") (pintype "bidirectional"))
    )
    (net (code "110") (name "unconnected-(IC1-RD12-Pad79)") (class "Default")
      (node (ref "IC1") (pin "79") (pinfunction "RD12_79") (pintype "bidirectional"))
    )
    (net (code "111") (name "unconnected-(IC1-RD13-Pad80)") (class "Default")
      (node (ref "IC1") (pin "80") (pinfunction "RD13_80") (pintype "bidirectional"))
    )
    (net (code "112") (name "unconnected-(IC1-RD15-Pad48)") (class "Default")
      (node (ref "IC1") (pin "48") (pinfunction "RD15_48") (pintype "bidirectional"))
    )
    (net (code "113") (name "unconnected-(IC1-RE9-Pad19)") (class "Default")
      (node (ref "IC1") (pin "19") (pinfunction "RE9_19") (pintype "bidirectional"))
    )
    (net (code "114") (name "unconnected-(IC1-RF0-Pad87)") (class "Default")
      (node (ref "IC1") (pin "87") (pinfunction "RF0_87") (pintype "bidirectional"))
    )
    (net (code "115") (name "unconnected-(IC1-RF1-Pad88)") (class "Default")
      (node (ref "IC1") (pin "88") (pinfunction "RF1_88") (pintype "bidirectional"))
    )
    (net (code "116") (name "unconnected-(IC1-RF12-Pad40)") (class "Default")
      (node (ref "IC1") (pin "40") (pinfunction "RF12_40") (pintype "bidirectional"))
    )
    (net (code "117") (name "unconnected-(IC1-RF13-Pad39)") (class "Default")
      (node (ref "IC1") (pin "39") (pinfunction "RF13_39") (pintype "bidirectional"))
    )
    (net (code "118") (name "unconnected-(IC1-RG0-Pad90)") (class "Default")
      (node (ref "IC1") (pin "90") (pinfunction "RG0_90") (pintype "bidirectional"))
    )
    (net (code "119") (name "unconnected-(IC1-RG1-Pad89)") (class "Default")
      (node (ref "IC1") (pin "89") (pinfunction "RG1_89") (pintype "bidirectional"))
    )
    (net (code "120") (name "unconnected-(IC1-RG12-Pad96)") (class "Default")
      (node (ref "IC1") (pin "96") (pinfunction "RG12_96") (pintype "bidirectional"))
    )
    (net (code "121") (name "unconnected-(IC1-RG13-Pad97)") (class "Default")
      (node (ref "IC1") (pin "97") (pinfunction "RG13_97") (pintype "bidirectional"))
    )
    (net (code "122") (name "unconnected-(IC1-RG14-Pad95)") (class "Default")
      (node (ref "IC1") (pin "95") (pinfunction "RG14_95") (pintype "bidirectional"))
    )
    (net (code "123") (name "unconnected-(IC1-RG15-Pad1)") (class "Default")
      (node (ref "IC1") (pin "1") (pinfunction "RG15_1") (pintype "bidirectional"))
    )
    (net (code "124") (name "unconnected-(IC1-TCK-Pad38)") (class "Default")
      (node (ref "IC1") (pin "38") (pinfunction "TCK_38") (pintype "input"))
    )
    (net (code "125") (name "unconnected-(IC1-TDI-Pad60)") (class "Default")
      (node (ref "IC1") (pin "60") (pinfunction "TDI_60") (pintype "input"))
    )
    (net (code "126") (name "unconnected-(IC1-TDO-Pad61)") (class "Default")
      (node (ref "IC1") (pin "61") (pinfunction "TDO_61") (pintype "output"))
    )
    (net (code "127") (name "unconnected-(IC1-TMS-Pad17)") (class "Default")
      (node (ref "IC1") (pin "17") (pinfunction "TMS_17") (pintype "input"))
    )
    (net (code "128") (name "unconnected-(J2-PadA1)") (class "Default")
      (node (ref "J2") (pin "A1") (pinfunction "A1_A1") (pintype "passive"))
    )
    (net (code "129") (name "unconnected-(J2-PadA2)") (class "Default")
      (node (ref "J2") (pin "A2") (pinfunction "A2_A2") (pintype "passive"))
    )
    (net (code "130") (name "unconnected-(J2-PadA10)") (class "Default")
      (node (ref "J2") (pin "A10") (pinfunction "A10_A10") (pintype "passive"))
    )
    (net (code "131") (name "unconnected-(J2-PadA15)") (class "Default")
      (node (ref "J2") (pin "A15") (pinfunction "A15_A15") (pintype "passive"))
    )
    (net (code "132") (name "unconnected-(J2-PadA16)") (class "Default")
      (node (ref "J2") (pin "A16") (pinfunction "A16_A16") (pintype "passive"))
    )
    (net (code "133") (name "unconnected-(J2-PadA17)") (class "Default")
      (node (ref "J2") (pin "A17") (pinfunction "A17_A17") (pintype "passive"))
    )
    (net (code "134") (name "unconnected-(J2-PadA18)") (class "Default")
      (node (ref "J2") (pin "A18") (pinfunction "A18_A18") (pintype "passive"))
    )
    (net (code "135") (name "unconnected-(J2-PadA19)") (class "Default")
      (node (ref "J2") (pin "A19") (pinfunction "A19_A19") (pintype "passive"))
    )
    (net (code "136") (name "unconnected-(J2-PadA20)") (class "Default")
      (node (ref "J2") (pin "A20") (pinfunction "A20_A20") (pintype "passive"))
    )
    (net (code "137") (name "unconnected-(J2-PadA21)") (class "Default")
      (node (ref "J2") (pin "A21") (pinfunction "A21_A21") (pintype "passive"))
    )
    (net (code "138") (name "unconnected-(J2-PadA22)") (class "Default")
      (node (ref "J2") (pin "A22") (pinfunction "A22_A22") (pintype "passive"))
    )
    (net (code "139") (name "unconnected-(J2-PadA23)") (class "Default")
      (node (ref "J2") (pin "A23") (pinfunction "A23_A23") (pintype "passive"))
    )
    (net (code "140") (name "unconnected-(J2-PadA24)") (class "Default")
      (node (ref "J2") (pin "A24") (pinfunction "A24_A24") (pintype "passive"))
    )
    (net (code "141") (name "unconnected-(J2-PadA25)") (class "Default")
      (node (ref "J2") (pin "A25") (pinfunction "A25_A25") (pintype "passive"))
    )
    (net (code "142") (name "unconnected-(J2-PadA26)") (class "Default")
      (node (ref "J2") (pin "A26") (pinfunction "A26_A26") (pintype "passive"))
    )
    (net (code "143") (name "unconnected-(J2-PadA27)") (class "Default")
      (node (ref "J2") (pin "A27") (pinfunction "A27_A27") (pintype "passive"))
    )
    (net (code "144") (name "unconnected-(J2-PadA28)") (class "Default")
      (node (ref "J2") (pin "A28") (pinfunction "A28_A28") (pintype "passive"))
    )
    (net (code "145") (name "unconnected-(J2-PadA29)") (class "Default")
      (node (ref "J2") (pin "A29") (pinfunction "A29_A29") (pintype "passive"))
    )
    (net (code "146") (name "unconnected-(J2-PadA30)") (class "Default")
      (node (ref "J2") (pin "A30") (pinfunction "A30_A30") (pintype "passive"))
    )
    (net (code "147") (name "unconnected-(J2-PadA31)") (class "Default")
      (node (ref "J2") (pin "A31") (pinfunction "A31_A31") (pintype "passive"))
    )
    (net (code "148") (name "unconnected-(J2-PadA32)") (class "Default")
      (node (ref "J2") (pin "A32") (pinfunction "A32_A32") (pintype "passive"))
    )
    (net (code "149") (name "unconnected-(J2-PadB10)") (class "Default")
      (node (ref "J2") (pin "B10") (pinfunction "B10_B10") (pintype "passive"))
    )
    (net (code "150") (name "unconnected-(J2-PadB15)") (class "Default")
      (node (ref "J2") (pin "B15") (pinfunction "B15_B15") (pintype "passive"))
    )
    (net (code "151") (name "unconnected-(J2-PadB16)") (class "Default")
      (node (ref "J2") (pin "B16") (pinfunction "B16_B16") (pintype "passive"))
    )
    (net (code "152") (name "unconnected-(J2-PadB17)") (class "Default")
      (node (ref "J2") (pin "B17") (pinfunction "B17_B17") (pintype "passive"))
    )
    (net (code "153") (name "unconnected-(J2-PadB18)") (class "Default")
      (node (ref "J2") (pin "B18") (pinfunction "B18_B18") (pintype "passive"))
    )
    (net (code "154") (name "unconnected-(J2-PadB19)") (class "Default")
      (node (ref "J2") (pin "B19") (pinfunction "B19_B19") (pintype "passive"))
    )
    (net (code "155") (name "unconnected-(J2-PadB20)") (class "Default")
      (node (ref "J2") (pin "B20") (pinfunction "B20_B20") (pintype "passive"))
    )
    (net (code "156") (name "unconnected-(J2-PadB21)") (class "Default")
      (node (ref "J2") (pin "B21") (pinfunction "B21_B21") (pintype "passive"))
    )
    (net (code "157") (name "unconnected-(J2-PadB22)") (class "Default")
      (node (ref "J2") (pin "B22") (pinfunction "B22_B22") (pintype "passive"))
    )
    (net (code "158") (name "unconnected-(J2-PadB23)") (class "Default")
      (node (ref "J2") (pin "B23") (pinfunction "B23_B23") (pintype "passive"))
    )
    (net (code "159") (name "unconnected-(J2-PadB24)") (class "Default")
      (node (ref "J2") (pin "B24") (pinfunction "B24_B24") (pintype "passive"))
    )
    (net (code "160") (name "unconnected-(J2-PadB25)") (class "Default")
      (node (ref "J2") (pin "B25") (pinfunction "B25_B25") (pintype "passive"))
    )
    (net (code "161") (name "unconnected-(J2-PadB26)") (class "Default")
      (node (ref "J2") (pin "B26") (pinfunction "B26_B26") (pintype "passive"))
    )
    (net (code "162") (name "unconnected-(J2-PadB27)") (class "Default")
      (node (ref "J2") (pin "B27") (pinfunction "B27_B27") (pintype "passive"))
    )
    (net (code "163") (name "unconnected-(J2-PadB28)") (class "Default")
      (node (ref "J2") (pin "B28") (pinfunction "B28_B28") (pintype "passive"))
    )
    (net (code "164") (name "unconnected-(J2-PadB29)") (class "Default")
      (node (ref "J2") (pin "B29") (pinfunction "B29_B29") (pintype "passive"))
    )
    (net (code "165") (name "unconnected-(J2-PadB30)") (class "Default")
      (node (ref "J2") (pin "B30") (pinfunction "B30_B30") (pintype "passive"))
    )
    (net (code "166") (name "unconnected-(J2-PadB31)") (class "Default")
      (node (ref "J2") (pin "B31") (pinfunction "B31_B31") (pintype "passive"))
    )
    (net (code "167") (name "unconnected-(J2-PadB32)") (class "Default")
      (node (ref "J2") (pin "B32") (pinfunction "B32_B32") (pintype "passive"))
    )
    (net (code "168") (name "unconnected-(J2-PadC10)") (class "Default")
      (node (ref "J2") (pin "C10") (pinfunction "C10_C10") (pintype "passive"))
    )
    (net (code "169") (name "unconnected-(J2-PadC15)") (class "Default")
      (node (ref "J2") (pin "C15") (pinfunction "C15_C15") (pintype "passive"))
    )
    (net (code "170") (name "unconnected-(J2-PadC16)") (class "Default")
      (node (ref "J2") (pin "C16") (pinfunction "C16_C16") (pintype "passive"))
    )
    (net (code "171") (name "unconnected-(J2-PadC17)") (class "Default")
      (node (ref "J2") (pin "C17") (pinfunction "C17_C17") (pintype "passive"))
    )
    (net (code "172") (name "unconnected-(J2-PadC18)") (class "Default")
      (node (ref "J2") (pin "C18") (pinfunction "C18_C18") (pintype "passive"))
    )
    (net (code "173") (name "unconnected-(J2-PadC19)") (class "Default")
      (node (ref "J2") (pin "C19") (pinfunction "C19_C19") (pintype "passive"))
    )
    (net (code "174") (name "unconnected-(J2-PadC20)") (class "Default")
      (node (ref "J2") (pin "C20") (pinfunction "C20_C20") (pintype "passive"))
    )
    (net (code "175") (name "unconnected-(J2-PadC21)") (class "Default")
      (node (ref "J2") (pin "C21") (pinfunction "C21_C21") (pintype "passive"))
    )
    (net (code "176") (name "unconnected-(J2-PadC22)") (class "Default")
      (node (ref "J2") (pin "C22") (pinfunction "C22_C22") (pintype "passive"))
    )
    (net (code "177") (name "unconnected-(J2-PadC23)") (class "Default")
      (node (ref "J2") (pin "C23") (pinfunction "C23_C23") (pintype "passive"))
    )
    (net (code "178") (name "unconnected-(J2-PadC24)") (class "Default")
      (node (ref "J2") (pin "C24") (pinfunction "C24_C24") (pintype "passive"))
    )
    (net (code "179") (name "unconnected-(J2-PadC25)") (class "Default")
      (node (ref "J2") (pin "C25") (pinfunction "C25_C25") (pintype "passive"))
    )
    (net (code "180") (name "unconnected-(J2-PadC26)") (class "Default")
      (node (ref "J2") (pin "C26") (pinfunction "C26_C26") (pintype "passive"))
    )
    (net (code "181") (name "unconnected-(J2-PadC27)") (class "Default")
      (node (ref "J2") (pin "C27") (pinfunction "C27_C27") (pintype "passive"))
    )
    (net (code "182") (name "unconnected-(J2-PadC28)") (class "Default")
      (node (ref "J2") (pin "C28") (pinfunction "C28_C28") (pintype "passive"))
    )
    (net (code "183") (name "unconnected-(J2-PadC29)") (class "Default")
      (node (ref "J2") (pin "C29") (pinfunction "C29_C29") (pintype "passive"))
    )
    (net (code "184") (name "unconnected-(J2-PadC30)") (class "Default")
      (node (ref "J2") (pin "C30") (pinfunction "C30_C30") (pintype "passive"))
    )
    (net (code "185") (name "unconnected-(J2-PadC31)") (class "Default")
      (node (ref "J2") (pin "C31") (pinfunction "C31_C31") (pintype "passive"))
    )
    (net (code "186") (name "unconnected-(J2-PadC32)") (class "Default")
      (node (ref "J2") (pin "C32") (pinfunction "C32_C32") (pintype "passive"))
    )
    (net (code "187") (name "unconnected-(JP1-Pad6)") (class "Default")
      (node (ref "JP1") (pin "6") (pinfunction "6_6") (pintype "passive"))
    )
    (net (code "188") (name "unconnected-(JP2-Pad6)") (class "Default")
      (node (ref "JP2") (pin "6") (pinfunction "6_6") (pintype "passive"))
    )
    (net (code "189") (name "unconnected-(PIC16-Pad2)") (class "Default")
      (node (ref "PIC16") (pin "2") (pinfunction "2_2") (pintype "passive"))
    )
    (net (code "190") (name "unconnected-(PIC16-Pad3)") (class "Default")
      (node (ref "PIC16") (pin "3") (pinfunction "3_3") (pintype "passive"))
    )
    (net (code "191") (name "unconnected-(PIC16-Pad11)") (class "Default")
      (node (ref "PIC16") (pin "11") (pinfunction "11_11") (pintype "passive"))
    )
    (net (code "192") (name "unconnected-(PIC16-Pad13)") (class "Default")
      (node (ref "PIC16") (pin "13") (pinfunction "13_13") (pintype "passive"))
    )
    (net (code "193") (name "unconnected-(U$1-CLK-Pad6)") (class "Default")
      (node (ref "U$1") (pin "6") (pinfunction "CLK_6") (pintype "bidirectional"))
    )
    (net (code "194") (name "unconnected-(U$1-CS-Pad5)") (class "Default")
      (node (ref "U$1") (pin "5") (pinfunction "CS_5") (pintype "bidirectional"))
    )
    (net (code "195") (name "unconnected-(U$1-GND2-Pad15)") (class "Default")
      (node (ref "U$1") (pin "15") (pinfunction "GND2_15") (pintype "bidirectional"))
    )
    (net (code "196") (name "unconnected-(U$1-MISO-Pad7)") (class "Default")
      (node (ref "U$1") (pin "7") (pinfunction "MISO_7") (pintype "bidirectional"))
    )
    (net (code "197") (name "unconnected-(U$1-MOSI-Pad8)") (class "Default")
      (node (ref "U$1") (pin "8") (pinfunction "MOSI_8") (pintype "bidirectional"))
    )
    (net (code "198") (name "unconnected-(U$1-NAV-Pad14)") (class "Default")
      (node (ref "U$1") (pin "14") (pinfunction "NAV_14") (pintype "bidirectional"))
    )
    (net (code "199") (name "unconnected-(U$1-RX1-Pad12)") (class "Default")
      (node (ref "U$1") (pin "12") (pinfunction "RX1_12") (pintype "bidirectional"))
    )
    (net (code "200") (name "unconnected-(U$1-SCL-Pad10)") (class "Default")
      (node (ref "U$1") (pin "10") (pinfunction "SCL_10") (pintype "bidirectional"))
    )
    (net (code "201") (name "unconnected-(U$1-SDA-Pad9)") (class "Default")
      (node (ref "U$1") (pin "9") (pinfunction "SDA_9") (pintype "bidirectional"))
    )
    (net (code "202") (name "unconnected-(U$1-TX1-Pad11)") (class "Default")
      (node (ref "U$1") (pin "11") (pinfunction "TX1_11") (pintype "bidirectional"))
    )
    (net (code "203") (name "unconnected-(U$1-VBAT-Pad16)") (class "Default")
      (node (ref "U$1") (pin "16") (pinfunction "VBAT_16") (pintype "bidirectional"))
    )
    (net (code "204") (name "unconnected-(X1-Pad14)") (class "Default")
      (node (ref "X1") (pin "14") (pinfunction "14_14") (pintype "passive"))
    )
    (net (code "205") (name "unconnected-(X1-Pad15)") (class "Default")
      (node (ref "X1") (pin "15") (pinfunction "15_15") (pintype "passive"))
    )
    (net (code "206") (name "unconnected-(X2-Pad3)") (class "Default")
      (node (ref "X2") (pin "3") (pinfunction "3_3") (pintype "passive"))
    )
    (net (code "207") (name "unconnected-(X2-Pad7)") (class "Default")
      (node (ref "X2") (pin "7") (pinfunction "7_7") (pintype "passive"))
    )
    (net (code "208") (name "unconnected-(X2-Pad10)") (class "Default")
      (node (ref "X2") (pin "10") (pinfunction "10_10") (pintype "passive"))
    )
    (net (code "209") (name "unconnected-(X2-Pad11)") (class "Default")
      (node (ref "X2") (pin "11") (pinfunction "11_11") (pintype "passive"))
    )
  )
)
